# PCBA-2121-01.net
KiCad netlist of a schematic drawn in Altium Designer
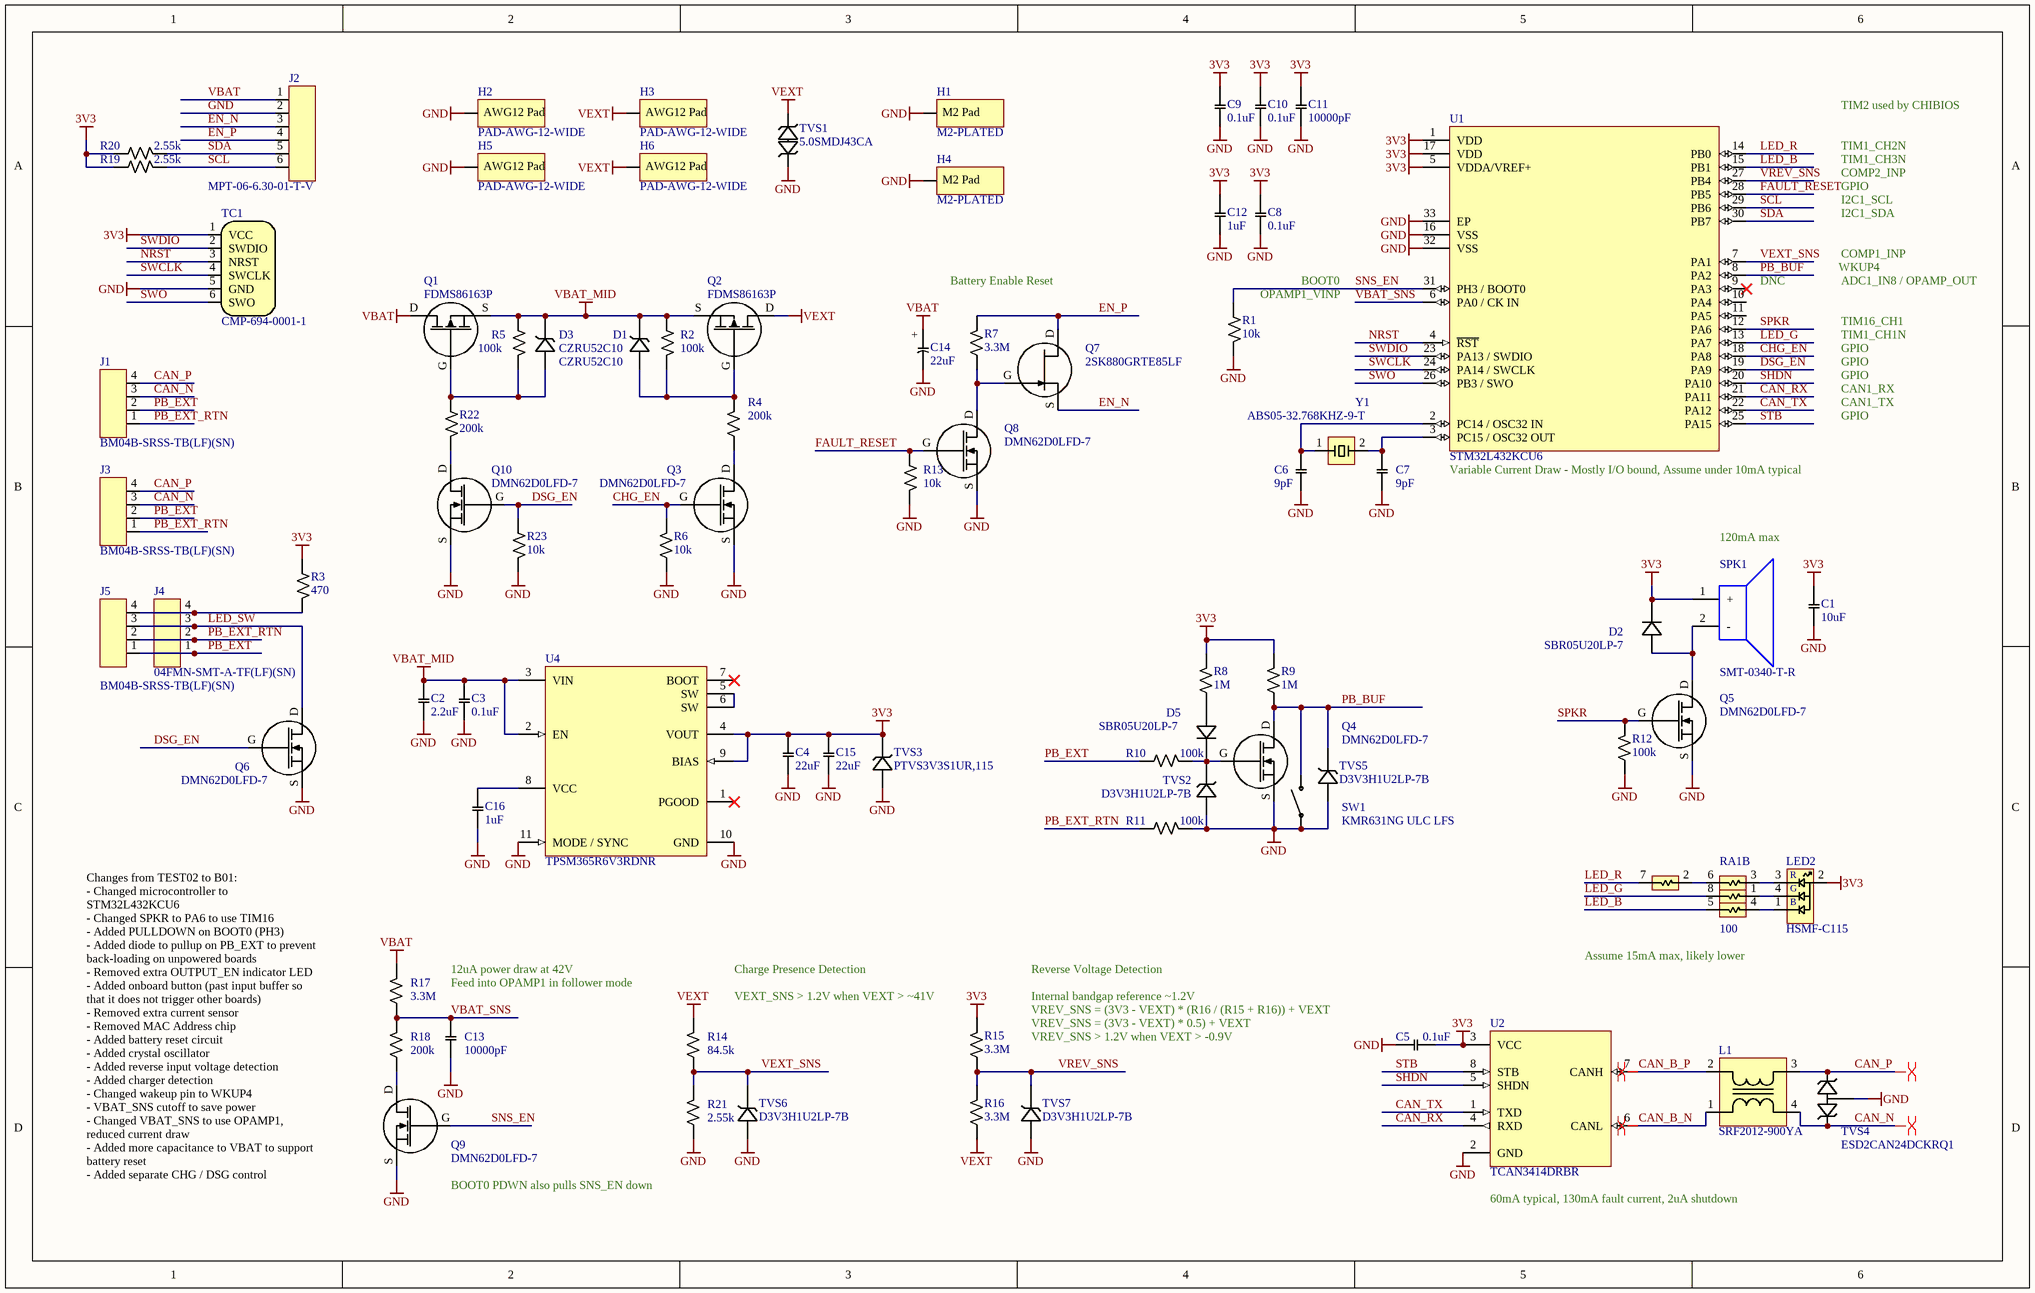
[diagram p0: PCBA-2121-01.SchDoc]

(export (version "E")
  (design (tool "Eeschema 10.0.6"))
  (components
    (comp (ref "C1")
      (value "C-10uf-X5R-16V-10%-0603")
      (footprint "C0603")
      (description "Capacitor Ceramic 10uF 16V X5R 10% SMD 0603")
      (fields (field (name "CAPACITANCE") "10uF") (field (name "TOLERANCE") "10%"))
      (libsource (lib "Hebi Robotics") (part "Capacitor"))
    )
    (comp (ref "C2")
      (value "C-2.2uf-X7R-100V-10%-1206")
      (footprint "C1206")
      (description "Capacitor Ceramic 2.2uF 100V X7R 10% SMD 1206")
      (fields (field (name "CAPACITANCE") "2.2uF") (field (name "TOLERANCE") "±10%"))
      (libsource (lib "Hebi Robotics") (part "Capacitor"))
    )
    (comp (ref "C3")
      (value "C-0.1uf-X7R-100V-10%-0603")
      (footprint "C0603")
      (description "Capacitor Ceramic 0.1uF 100V X7R 10% SMD 0603")
      (fields (field (name "CAPACITANCE") "0.1uF") (field (name "TOLERANCE") "±10%"))
      (libsource (lib "Hebi Robotics") (part "Capacitor"))
    )
    (comp (ref "C4")
      (value "C-22uf-X5R-25V-20%-1206")
      (footprint "C1206")
      (description "Capacitor Ceramic 22uF 25V X5R 20% SMD 1206")
      (fields (field (name "CAPACITANCE") "22uF") (field (name "TOLERANCE") "20%"))
      (libsource (lib "Hebi Robotics") (part "Capacitor"))
    )
    (comp (ref "C5")
      (value "C-0.1uf-X7R-25V-10%-0402")
      (footprint "C0402")
      (description "Capacitor Ceramic 0.1uF 25V X7R 10% SMD 0402")
      (fields (field (name "CAPACITANCE") "0.1uF") (field (name "TOLERANCE") "10%"))
      (libsource (lib "Hebi Robotics") (part "Capacitor"))
    )
    (comp (ref "C6")
      (value "C-9pf-NP0-50V-0.1pF-0402")
      (footprint "C0402")
      (description "Capacitor Ceramic 9pF 50V NP0 ±0.1pF SMD 0402")
      (fields (field (name "CAPACITANCE") "9pF") (field (name "TOLERANCE") "±0.1pF"))
      (libsource (lib "Hebi Robotics") (part "Capacitor"))
    )
    (comp (ref "C7")
      (value "C-9pf-NP0-50V-0.1pF-0402")
      (footprint "C0402")
      (description "Capacitor Ceramic 9pF 50V NP0 ±0.1pF SMD 0402")
      (fields (field (name "CAPACITANCE") "9pF") (field (name "TOLERANCE") "±0.1pF"))
      (libsource (lib "Hebi Robotics") (part "Capacitor"))
    )
    (comp (ref "C8")
      (value "C-0.1uf-X7R-25V-10%-0402")
      (footprint "C0402")
      (description "Capacitor Ceramic 0.1uF 25V X7R 10% SMD 0402")
      (fields (field (name "CAPACITANCE") "0.1uF") (field (name "TOLERANCE") "10%"))
      (libsource (lib "Hebi Robotics") (part "Capacitor"))
    )
    (comp (ref "C9")
      (value "C-0.1uf-X7R-25V-10%-0402")
      (footprint "C0402")
      (description "Capacitor Ceramic 0.1uF 25V X7R 10% SMD 0402")
      (fields (field (name "CAPACITANCE") "0.1uF") (field (name "TOLERANCE") "10%"))
      (libsource (lib "Hebi Robotics") (part "Capacitor"))
    )
    (comp (ref "C10")
      (value "C-0.1uf-X7R-25V-10%-0402")
      (footprint "C0402")
      (description "Capacitor Ceramic 0.1uF 25V X7R 10% SMD 0402")
      (fields (field (name "CAPACITANCE") "0.1uF") (field (name "TOLERANCE") "10%"))
      (libsource (lib "Hebi Robotics") (part "Capacitor"))
    )
    (comp (ref "C11")
      (value "C-10000pf-X7R-50V-10%-0402")
      (footprint "C0402")
      (description "Capacitor Ceramic 10000pF 50V X7R 10% SMD 0402")
      (fields (field (name "TOLERANCE") "10%") (field (name "CAPACITANCE") "10000pF"))
      (libsource (lib "Hebi Robotics") (part "Capacitor"))
    )
    (comp (ref "C12")
      (value "C-1uf-X5R-25V-10%-0402")
      (footprint "C0402")
      (description "Capacitor Ceramic 1uF 25V X5R 10% SMD 0402")
      (fields (field (name "CAPACITANCE") "1uF") (field (name "TOLERANCE") "±10%"))
      (libsource (lib "Hebi Robotics") (part "Capacitor"))
    )
    (comp (ref "C13")
      (value "C-10000pf-X7R-50V-10%-0402")
      (footprint "C0402")
      (description "Capacitor Ceramic 10000pF 50V X7R 10% SMD 0402")
      (fields (field (name "CAPACITANCE") "10000pF") (field (name "TOLERANCE") "10%"))
      (libsource (lib "Hebi Robotics") (part "Capacitor"))
    )
    (comp (ref "C14")
      (value "UCM1H220MCL1GS")
      (footprint "CAPAE5753X61L")
      (description "CAP ALUM 22UF 20% 50V SMD")
      (fields
        (field (name "CAPACITANCE") "22uF")
        (field (name "TOLERANCE") "20%")
        (field (name "VOLTAGE") "50V")
      )
      (libsource (lib "Hebi Robotics") (part "Capacitor_Polarized"))
    )
    (comp (ref "C15")
      (value "C-22uf-X5R-25V-20%-1206")
      (footprint "C1206")
      (description "Capacitor Ceramic 22uF 25V X5R 20% SMD 1206")
      (fields (field (name "CAPACITANCE") "22uF") (field (name "TOLERANCE") "20%"))
      (libsource (lib "Hebi Robotics") (part "Capacitor"))
    )
    (comp (ref "C16")
      (value "C-1uf-X5R-25V-10%-0402")
      (footprint "C0402")
      (description "Capacitor Ceramic 1uF 25V X5R 10% SMD 0402")
      (fields (field (name "CAPACITANCE") "1uF") (field (name "TOLERANCE") "±10%"))
      (libsource (lib "Hebi Robotics") (part "Capacitor"))
    )
    (comp (ref "D1")
      (value "CZRU52C10")
      (footprint "CZRU52C10")
      (description "DIODE ZENER 10V 150MW 0603")
      (libsource (lib "Hebi Robotics") (part "ZENER"))
    )
    (comp (ref "D2")
      (value "SBR05U20LP-7")
      (footprint "DFN1006-2_DIODES")
      (description "DIODE SBR 20V 500MA 2DFN")
      (libsource (lib "Hebi Robotics") (part "DIODE"))
    )
    (comp (ref "D3")
      (value "CZRU52C10")
      (footprint "CZRU52C10")
      (description "DIODE ZENER 10V 150MW 0603")
      (libsource (lib "Hebi Robotics") (part "ZENER"))
    )
    (comp (ref "D5")
      (value "SBR05U20LP-7")
      (footprint "DFN1006-2_DIODES")
      (description "DIODE SBR 20V 500MA 2DFN")
      (libsource (lib "Hebi Robotics") (part "DIODE"))
    )
    (comp (ref "H1")
      (value "M2-PLATED")
      (footprint "M2-PLATED-NORMAL")
      (description "M2 Size Screw Hole, Normal Fit, Plated")
      (libsource (lib "Hebi Robotics") (part "MOUNTING_HOLE"))
    )
    (comp (ref "H2")
      (value "PAD-AWG-12-WIDE")
      (footprint "AWG-12-With-Wire")
      (description "AWG 12 Hole with Wider Pad")
      (libsource (lib "Hebi Robotics") (part "WIRE_PAD"))
    )
    (comp (ref "H3")
      (value "PAD-AWG-12-WIDE")
      (footprint "AWG-12-With-Wire")
      (description "AWG 12 Hole with Wider Pad")
      (libsource (lib "Hebi Robotics") (part "WIRE_PAD"))
    )
    (comp (ref "H4")
      (value "M2-PLATED")
      (footprint "M2-PLATED-NORMAL")
      (description "M2 Size Screw Hole, Normal Fit, Plated")
      (libsource (lib "Hebi Robotics") (part "MOUNTING_HOLE"))
    )
    (comp (ref "H5")
      (value "PAD-AWG-12-WIDE")
      (footprint "AWG-12-With-Wire")
      (description "AWG 12 Hole with Wider Pad")
      (libsource (lib "Hebi Robotics") (part "WIRE_PAD"))
    )
    (comp (ref "H6")
      (value "PAD-AWG-12-WIDE")
      (footprint "AWG-12-With-Wire")
      (description "AWG 12 Hole with Wider Pad")
      (libsource (lib "Hebi Robotics") (part "WIRE_PAD"))
    )
    (comp (ref "J1")
      (value "BM04B-SRSS-TB(LF)(SN)")
      (footprint "BM04B-SRSS-TB")
      (description "CONN HEADER SH 4POS TOP 1MM TIN")
      (fields (field (name "MANUFACTURER") "JST Sales America Inc"))
      (libsource (lib "Hebi Robotics") (part "CONN_1_ROW_004_POS"))
    )
    (comp (ref "J2")
      (value "MPT-06-6.30-01-T-V")
      (footprint "MPT-06-6.30-01-T-V-Footprint-1")
      (description "5.00 MM POWERSTRIP/30 A DUAL BL")
      (libsource (lib "Hebi Robotics") (part "CONN_1_ROW_006_POS"))
    )
    (comp (ref "J3")
      (value "BM04B-SRSS-TB(LF)(SN)")
      (footprint "BM04B-SRSS-TB")
      (description "CONN HEADER SH 4POS TOP 1MM TIN")
      (fields (field (name "MANUFACTURER") "JST Sales America Inc"))
      (libsource (lib "Hebi Robotics") (part "CONN_1_ROW_004_POS"))
    )
    (comp (ref "J4")
      (value "04FMN-SMT-A-TF(LF)(SN)")
      (footprint "04FMN-SMT-A-TF(LF)(SN)-Footprint-1")
      (description "Ffc / Fpc Board Connector, Fmn Series, Surface Mount, Receptacle, 4, 1 Mm Rohs Compliant: Yes")
      (libsource (lib "Hebi Robotics") (part "CONN_1_ROW_004_POS"))
    )
    (comp (ref "J5")
      (value "BM04B-SRSS-TB(LF)(SN)")
      (footprint "BM04B-SRSS-TB")
      (description "CONN HEADER SH 4POS TOP 1MM TIN")
      (fields (field (name "MANUFACTURER") "JST Sales America Inc"))
      (libsource (lib "Hebi Robotics") (part "CONN_1_ROW_004_POS"))
    )
    (comp (ref "L1")
      (value "SRF2012-900YA")
      (footprint "FP-SRF2012A-MFG")
      (description "CMC 400MA 2LN 90 OHM SMD")
      (libsource (lib "Hebi Robotics") (part "CM_CHOKE_4PIN"))
    )
    (comp (ref "LED2")
      (value "HSMF-C115")
      (footprint "HSMF-C115")
      (description "LED RGB DIFFUSED CHIP SMD R/A")
      (libsource (lib "Hebi Robotics") (part "HSMF-C115"))
    )
    (comp (ref "Q1")
      (value "FDMS86163P")
      (footprint "FDMS86300DC")
      (description "MOSFET P-CH 100V 7.9A POWER56")
      (libsource (lib "Hebi Robotics") (part "P_MOSFET"))
    )
    (comp (ref "Q2")
      (value "FDMS86163P")
      (footprint "FDMS86300DC")
      (description "MOSFET P-CH 100V 7.9A POWER56")
      (libsource (lib "Hebi Robotics") (part "P_MOSFET"))
    )
    (comp (ref "Q3")
      (value "DMN62D0LFD-7")
      (footprint "DMN62D0LFD-7-Footprint-1")
      (description "MOSFET N-CH 60V 310MA 3DFN")
      (libsource (lib "Hebi Robotics") (part "N_MOSFET"))
    )
    (comp (ref "Q4")
      (value "DMN62D0LFD-7")
      (footprint "DMN62D0LFD-7-Footprint-1")
      (description "MOSFET N-CH 60V 310MA 3DFN")
      (libsource (lib "Hebi Robotics") (part "N_MOSFET"))
    )
    (comp (ref "Q5")
      (value "DMN62D0LFD-7")
      (footprint "DMN62D0LFD-7-Footprint-1")
      (description "MOSFET N-CH 60V 310MA 3DFN")
      (libsource (lib "Hebi Robotics") (part "N_MOSFET"))
    )
    (comp (ref "Q6")
      (value "DMN62D0LFD-7")
      (footprint "DMN62D0LFD-7-Footprint-1")
      (description "MOSFET N-CH 60V 310MA 3DFN")
      (libsource (lib "Hebi Robotics") (part "N_MOSFET"))
    )
    (comp (ref "Q7")
      (value "2SK880GRTE85LF")
      (footprint "SOT65P205X100-3L")
      (description "JFET N-CH 50V SC70")
      (libsource (lib "Hebi Robotics") (part "N_JFET"))
    )
    (comp (ref "Q8")
      (value "DMN62D0LFD-7")
      (footprint "DMN62D0LFD-7-Footprint-1")
      (description "MOSFET N-CH 60V 310MA 3DFN")
      (libsource (lib "Hebi Robotics") (part "N_MOSFET"))
    )
    (comp (ref "Q9")
      (value "DMN62D0LFD-7")
      (footprint "DMN62D0LFD-7-Footprint-1")
      (description "MOSFET N-CH 60V 310MA 3DFN")
      (libsource (lib "Hebi Robotics") (part "N_MOSFET"))
    )
    (comp (ref "Q10")
      (value "DMN62D0LFD-7")
      (footprint "DMN62D0LFD-7-Footprint-1")
      (description "MOSFET N-CH 60V 310MA 3DFN")
      (libsource (lib "Hebi Robotics") (part "N_MOSFET"))
    )
    (comp (ref "R1")
      (value "R-10k-1%-0.063w-0402")
      (footprint "R0402")
      (description "Resistor 0402 10k Ohm 1% 1-16 Watt")
      (fields
        (field (name "POWER") "0.063W, 1/16W")
        (field (name "RESISTANCE") "10k")
        (field (name "TOLERANCE") "1%")
      )
      (libsource (lib "Hebi Robotics") (part "Resistor"))
    )
    (comp (ref "R2")
      (value "R-100k-1%-0.063w-0402")
      (footprint "R0402")
      (description "Resistor 0402 100k Ohm 1% 1-16 Watt")
      (fields
        (field (name "POWER") "0.063W, 1/16W")
        (field (name "RESISTANCE") "100k")
        (field (name "TOLERANCE") "1%")
      )
      (libsource (lib "Hebi Robotics") (part "Resistor"))
    )
    (comp (ref "R3")
      (value "R-470-1%-0.063w-0402")
      (footprint "R0402")
      (description "Resistor 0402 470 Ohm 1% 1-16 Watt")
      (fields
        (field (name "POWER") "0.063W, 1/16W")
        (field (name "TOLERANCE") "1%")
        (field (name "RESISTANCE") "470")
      )
      (libsource (lib "Hebi Robotics") (part "Resistor"))
    )
    (comp (ref "R4")
      (value "R-200k-1%-0.063w-0402")
      (footprint "R0402")
      (description "Resistor 0402 200k Ohm 1% 1-16 Watt")
      (fields
        (field (name "POWER") "0.063W, 1/16W")
        (field (name "RESISTANCE") "200k")
        (field (name "TOLERANCE") "1%")
      )
      (libsource (lib "Hebi Robotics") (part "Resistor"))
    )
    (comp (ref "R5")
      (value "R-100k-1%-0.063w-0402")
      (footprint "R0402")
      (description "Resistor 0402 100k Ohm 1% 1-16 Watt")
      (fields
        (field (name "POWER") "0.063W, 1/16W")
        (field (name "RESISTANCE") "100k")
        (field (name "TOLERANCE") "1%")
      )
      (libsource (lib "Hebi Robotics") (part "Resistor"))
    )
    (comp (ref "R6")
      (value "R-10k-1%-0.063w-0402")
      (footprint "R0402")
      (description "Resistor 0402 10k Ohm 1% 1-16 Watt")
      (fields
        (field (name "POWER") "0.063W, 1/16W")
        (field (name "RESISTANCE") "10k")
        (field (name "TOLERANCE") "1%")
      )
      (libsource (lib "Hebi Robotics") (part "Resistor"))
    )
    (comp (ref "R7")
      (value "R-3.3M-1%-0.063w-0402")
      (footprint "R0402")
      (description "Resistor 0402 3.3M Ohm 1% 1-16 Watt")
      (fields (field (name "POWER") "0.063W, 1/16W") (field (name "RESISTANCE") "3.3M"))
      (libsource (lib "Hebi Robotics") (part "Resistor"))
    )
    (comp (ref "R8")
      (value "R-1M-1%-0.063w-0402")
      (footprint "R0402")
      (description "Resistor 0402 1M Ohm 1% 1-16 Watt")
      (fields
        (field (name "RESISTANCE") "1M")
        (field (name "POWER") "0.063W, 1/16W")
        (field (name "TOLERANCE") "1%")
      )
      (libsource (lib "Hebi Robotics") (part "Resistor"))
    )
    (comp (ref "R9")
      (value "R-1M-1%-0.063w-0402")
      (footprint "R0402")
      (description "Resistor 0402 1M Ohm 1% 1-16 Watt")
      (fields
        (field (name "RESISTANCE") "1M")
        (field (name "POWER") "0.063W, 1/16W")
        (field (name "TOLERANCE") "1%")
      )
      (libsource (lib "Hebi Robotics") (part "Resistor"))
    )
    (comp (ref "R10")
      (value "R-100k-1%-0.063w-0402")
      (footprint "R0402")
      (description "Resistor 0402 100k Ohm 1% 1-16 Watt")
      (fields
        (field (name "POWER") "0.063W, 1/16W")
        (field (name "RESISTANCE") "100k")
        (field (name "TOLERANCE") "1%")
      )
      (libsource (lib "Hebi Robotics") (part "Resistor"))
    )
    (comp (ref "R11")
      (value "R-100k-1%-0.063w-0402")
      (footprint "R0402")
      (description "Resistor 0402 100k Ohm 1% 1-16 Watt")
      (fields
        (field (name "POWER") "0.063W, 1/16W")
        (field (name "RESISTANCE") "100k")
        (field (name "TOLERANCE") "1%")
      )
      (libsource (lib "Hebi Robotics") (part "Resistor"))
    )
    (comp (ref "R12")
      (value "R-100k-1%-0.063w-0402")
      (footprint "R0402")
      (description "Resistor 0402 100k Ohm 1% 1-16 Watt")
      (fields
        (field (name "POWER") "0.063W, 1/16W")
        (field (name "TOLERANCE") "1%")
        (field (name "RESISTANCE") "100k")
      )
      (libsource (lib "Hebi Robotics") (part "Resistor"))
    )
    (comp (ref "R13")
      (value "R-10k-1%-0.063w-0402")
      (footprint "R0402")
      (description "Resistor 0402 10k Ohm 1% 1-16 Watt")
      (fields
        (field (name "POWER") "0.063W, 1/16W")
        (field (name "RESISTANCE") "10k")
        (field (name "TOLERANCE") "1%")
      )
      (libsource (lib "Hebi Robotics") (part "Resistor"))
    )
    (comp (ref "R14")
      (value "R-84.5k-1%-0.063w-0402")
      (footprint "R0402")
      (description "Resistor 0402 84.5k Ohm 1% 1-16 Watt")
      (fields (field (name "RESISTANCE") "84.5k") (field (name "POWER") "0.063W, 1/16W"))
      (libsource (lib "Hebi Robotics") (part "Resistor"))
    )
    (comp (ref "R15")
      (value "R-3.3M-1%-0.063w-0402")
      (footprint "R0402")
      (description "Resistor 0402 3.3M Ohm 1% 1-16 Watt")
      (fields (field (name "POWER") "0.063W, 1/16W") (field (name "RESISTANCE") "3.3M"))
      (libsource (lib "Hebi Robotics") (part "Resistor"))
    )
    (comp (ref "R16")
      (value "R-3.3M-1%-0.063w-0402")
      (footprint "R0402")
      (description "Resistor 0402 3.3M Ohm 1% 1-16 Watt")
      (fields (field (name "POWER") "0.063W, 1/16W") (field (name "RESISTANCE") "3.3M"))
      (libsource (lib "Hebi Robotics") (part "Resistor"))
    )
    (comp (ref "R17")
      (value "R-3.3M-1%-0.063w-0402")
      (footprint "R0402")
      (description "Resistor 0402 3.3M Ohm 1% 1-16 Watt")
      (fields (field (name "POWER") "0.063W, 1/16W") (field (name "RESISTANCE") "3.3M"))
      (libsource (lib "Hebi Robotics") (part "Resistor"))
    )
    (comp (ref "R18")
      (value "R-200k-1%-0.063w-0402")
      (footprint "R0402")
      (description "Resistor 0402 200k Ohm 1% 1-16 Watt")
      (fields
        (field (name "POWER") "0.063W, 1/16W")
        (field (name "RESISTANCE") "200k")
        (field (name "TOLERANCE") "1%")
      )
      (libsource (lib "Hebi Robotics") (part "Resistor"))
    )
    (comp (ref "R19")
      (value "R-2.55k-1%-0.063w-0402")
      (footprint "R0402")
      (description "Resistor 0402 2.55k Ohm 1% 1-16 Watt")
      (fields (field (name "RESISTANCE") "2.55k") (field (name "POWER") "0.063W, 1/16W"))
      (libsource (lib "Hebi Robotics") (part "Resistor"))
    )
    (comp (ref "R20")
      (value "R-2.55k-1%-0.063w-0402")
      (footprint "R0402")
      (description "Resistor 0402 2.55k Ohm 1% 1-16 Watt")
      (fields (field (name "RESISTANCE") "2.55k") (field (name "POWER") "0.063W, 1/16W"))
      (libsource (lib "Hebi Robotics") (part "Resistor"))
    )
    (comp (ref "R21")
      (value "R-2.55k-1%-0.063w-0402")
      (footprint "R0402")
      (description "Resistor 0402 2.55k Ohm 1% 1-16 Watt")
      (fields (field (name "POWER") "0.063W, 1/16W") (field (name "RESISTANCE") "2.55k"))
      (libsource (lib "Hebi Robotics") (part "Resistor"))
    )
    (comp (ref "R22")
      (value "R-200k-1%-0.063w-0402")
      (footprint "R0402")
      (description "Resistor 0402 200k Ohm 1% 1-16 Watt")
      (fields
        (field (name "POWER") "0.063W, 1/16W")
        (field (name "RESISTANCE") "200k")
        (field (name "TOLERANCE") "1%")
      )
      (libsource (lib "Hebi Robotics") (part "Resistor"))
    )
    (comp (ref "R23")
      (value "R-10k-1%-0.063w-0402")
      (footprint "R0402")
      (description "Resistor 0402 10k Ohm 1% 1-16 Watt")
      (fields
        (field (name "POWER") "0.063W, 1/16W")
        (field (name "RESISTANCE") "10k")
        (field (name "TOLERANCE") "1%")
      )
      (libsource (lib "Hebi Robotics") (part "Resistor"))
    )
    (comp (ref "RA1")
      (value "RA-4-C-100-5%-0.063w-0804")
      (footprint "741C083")
      (description "100 ohm Resistor Array 4 Element Concave 5%  1-16Watt 0804")
      (fields (field (name "POWER") "0.063W") (field (name "RESISTANCE") "100"))
      (libsource (lib "Hebi Robotics") (part "RA4"))
    )
    (comp (ref "SPK1")
      (value "SMT-0340-T-R")
      (footprint "SMT-0340-T-R")
      (description "BUZZER MAGNETIC 3V 3.2X3.2MM SMD")
      (fields (field (name "VOLTAGE") "3V"))
      (libsource (lib "Hebi Robotics") (part "Speaker"))
    )
    (comp (ref "SW1")
      (value "KMR631NG ULC LFS")
      (footprint "KMR6_CK")
      (description "SWITCH TACTILE SPST-NO 50MA 32V")
      (fields (field (name "MANUFACTURER") "ITT C&K"))
      (libsource (lib "Hebi Robotics") (part "SPST_NO"))
    )
    (comp (ref "TC1")
      (value "CMP-694-0001-1")
      (footprint "TC2030-MCP-NL_SMALL")
      (description "TC2030-MCP-NL")
      (fields (field (name "MANUFACTURER PART NUMBER") "TC2030-MCP-NL_SMALL"))
      (libsource (lib "Hebi Robotics") (part "TC2030-MCP-NL"))
    )
    (comp (ref "TVS1")
      (value "5.0SMDJ43CA")
      (footprint "DIOM6959X26L")
      (description "TVS DIODE 43VWM 69.4VC DO214AB")
      (libsource (lib "Hebi Robotics") (part "TVS_BI"))
    )
    (comp (ref "TVS2")
      (value "D3V3H1U2LP-7B")
      (footprint "DFN70P101X53-2N")
      (description "TVS DIODE 3.3V 10V DFN1006-2")
      (libsource (lib "Hebi Robotics") (part "TVS"))
    )
    (comp (ref "TVS3")
      (value "PTVS3V3S1UR,115")
      (footprint "SOD-123W_NXP")
      (description "TVS DIODE 3.3VWM 8VC SOD123W")
      (libsource (lib "Hebi Robotics") (part "TVS"))
    )
    (comp (ref "TVS4")
      (value "ESD2CAN24DCKRQ1")
      (footprint "SOT65P210X90-3L")
      (description "TVS DIODE 24VWM 37VC CAN SC703")
      (libsource (lib "Hebi Robotics") (part "ESD2CAN24DCKRQ1-Symbol-1"))
    )
    (comp (ref "TVS5")
      (value "D3V3H1U2LP-7B")
      (footprint "DFN70P101X53-2N")
      (description "TVS DIODE 3.3V 10V DFN1006-2")
      (libsource (lib "Hebi Robotics") (part "TVS"))
    )
    (comp (ref "TVS6")
      (value "D3V3H1U2LP-7B")
      (footprint "DFN70P101X53-2N")
      (description "TVS DIODE 3.3V 10V DFN1006-2")
      (libsource (lib "Hebi Robotics") (part "TVS"))
    )
    (comp (ref "TVS7")
      (value "D3V3H1U2LP-7B")
      (footprint "DFN70P101X53-2N")
      (description "TVS DIODE 3.3V 10V DFN1006-2")
      (libsource (lib "Hebi Robotics") (part "TVS"))
    )
    (comp (ref "U1")
      (value "STM32L432KCU6")
      (footprint "QFN50P500X500X60_HS-33L")
      (description "IC MCU 32BIT 256KB FLSH 32UFQFPN")
      (libsource (lib "Hebi Robotics") (part "STM32L412K8U6"))
    )
    (comp (ref "U2")
      (value "TCAN3414DRBR")
      (footprint "SON65P300X100_HS-9L")
      (description "IC TRANSCEIVER HALF 1/1 8SON")
      (libsource (lib "Hebi Robotics") (part "TCAN3414DRBR-Symbol-1"))
    )
    (comp (ref "U4")
      (value "TPSM365R6V3RDNR")
      (footprint "TPSM365R6V3RDNR-Footprint-1")
      (description "3-V TO 65-V INPUT, 3V3 OUT, 300mA")
      (libsource (lib "Hebi Robotics") (part "TPSM365R6V3RDNR-Symbol-1"))
    )
    (comp (ref "Y1")
      (value "ABS05-32.768KHZ-9-T")
      (footprint "ABS05-32.768KHZ-9-T-Footprint-1")
      (description "CRYSTAL 32.7680KHZ 9PF SMD")
      (libsource (lib "Hebi Robotics") (part "CRYSTAL"))
    )
  )
  (nets
    (net (code "1") (name "/CAN_B_N") (class "Default")
      (node (ref "L1") (pin "1") (pinfunction "1_1") (pintype "passive"))
      (node (ref "U2") (pin "6") (pinfunction "CANL_6") (pintype "bidirectional"))
    )
    (net (code "2") (name "/CAN_B_P") (class "Default")
      (node (ref "L1") (pin "2") (pinfunction "2_2") (pintype "passive"))
      (node (ref "U2") (pin "7") (pinfunction "CANH_7") (pintype "bidirectional"))
    )
    (net (code "3") (name "/CAN_N") (class "Default")
      (node (ref "J1") (pin "3") (pinfunction "3_3") (pintype "passive"))
      (node (ref "J3") (pin "3") (pinfunction "3_3") (pintype "passive"))
      (node (ref "L1") (pin "4") (pinfunction "4_4") (pintype "passive"))
      (node (ref "TVS4") (pin "2") (pinfunction "2_2") (pintype "passive"))
    )
    (net (code "4") (name "/CAN_P") (class "Default")
      (node (ref "J1") (pin "4") (pinfunction "4_4") (pintype "passive"))
      (node (ref "J3") (pin "4") (pinfunction "4_4") (pintype "passive"))
      (node (ref "L1") (pin "3") (pinfunction "3_3") (pintype "passive"))
      (node (ref "TVS4") (pin "1") (pinfunction "1_1") (pintype "passive"))
    )
    (net (code "5") (name "/CAN_RX") (class "Default")
      (node (ref "U1") (pin "21") (pinfunction "PA11_21") (pintype "bidirectional"))
      (node (ref "U2") (pin "4") (pinfunction "RXD_4") (pintype "output"))
    )
    (net (code "6") (name "/CAN_TX") (class "Default")
      (node (ref "U1") (pin "22") (pinfunction "PA12_22") (pintype "bidirectional"))
      (node (ref "U2") (pin "1") (pinfunction "TXD_1") (pintype "input"))
    )
    (net (code "7") (name "/CHG_EN") (class "Default")
      (node (ref "Q3") (pin "G") (pinfunction "G_G") (pintype "passive"))
      (node (ref "R6") (pin "2") (pinfunction "2_2") (pintype "passive"))
      (node (ref "U1") (pin "18") (pinfunction "PA8_18") (pintype "bidirectional"))
    )
    (net (code "8") (name "/DSG_EN") (class "Default")
      (node (ref "Q10") (pin "G") (pinfunction "G_G") (pintype "passive"))
      (node (ref "Q6") (pin "G") (pinfunction "G_G") (pintype "passive"))
      (node (ref "R23") (pin "2") (pinfunction "2_2") (pintype "passive"))
      (node (ref "U1") (pin "19") (pinfunction "PA9_19") (pintype "bidirectional"))
    )
    (net (code "9") (name "/EN_N") (class "Default")
      (node (ref "J2") (pin "3") (pinfunction "3_3") (pintype "passive"))
      (node (ref "Q7") (pin "S") (pinfunction "S_S") (pintype "passive"))
    )
    (net (code "10") (name "/EN_P") (class "Default")
      (node (ref "J2") (pin "4") (pinfunction "4_4") (pintype "passive"))
      (node (ref "Q7") (pin "D") (pinfunction "D_D") (pintype "passive"))
      (node (ref "R7") (pin "2") (pinfunction "2_2") (pintype "passive"))
    )
    (net (code "11") (name "/FAULT_RESET") (class "Default")
      (node (ref "Q8") (pin "G") (pinfunction "G_G") (pintype "passive"))
      (node (ref "R13") (pin "1") (pinfunction "1_1") (pintype "passive"))
      (node (ref "U1") (pin "28") (pinfunction "PB5_28") (pintype "bidirectional"))
    )
    (net (code "12") (name "/LED_B") (class "Default")
      (node (ref "RA1") (pin "5") (pinfunction "5_5") (pintype "passive"))
      (node (ref "U1") (pin "15") (pinfunction "PB1_15") (pintype "bidirectional"))
    )
    (net (code "13") (name "/LED_G") (class "Default")
      (node (ref "RA1") (pin "8") (pinfunction "8_8") (pintype "passive"))
      (node (ref "U1") (pin "13") (pinfunction "PA7_13") (pintype "bidirectional"))
    )
    (net (code "14") (name "/LED_R") (class "Default")
      (node (ref "RA1") (pin "7") (pinfunction "7_7") (pintype "passive"))
      (node (ref "U1") (pin "14") (pinfunction "PB0_14") (pintype "bidirectional"))
    )
    (net (code "15") (name "/LED_SW") (class "Default")
      (node (ref "J4") (pin "3") (pinfunction "3_3") (pintype "passive"))
      (node (ref "J5") (pin "3") (pinfunction "3_3") (pintype "passive"))
      (node (ref "Q6") (pin "D") (pinfunction "D_D") (pintype "passive"))
    )
    (net (code "16") (name "/NRST") (class "Default")
      (node (ref "TC1") (pin "3") (pinfunction "NRST_3") (pintype "passive"))
      (node (ref "U1") (pin "4") (pinfunction "~{RST}_4") (pintype "input"))
    )
    (net (code "17") (name "/PB_BUF") (class "Default")
      (node (ref "Q4") (pin "D") (pinfunction "D_D") (pintype "passive"))
      (node (ref "R9") (pin "1") (pinfunction "1_1") (pintype "passive"))
      (node (ref "SW1") (pin "2") (pinfunction "2_2") (pintype "passive"))
      (node (ref "TVS5") (pin "C") (pinfunction "C_C") (pintype "passive"))
      (node (ref "U1") (pin "8") (pinfunction "PA2_8") (pintype "bidirectional"))
    )
    (net (code "18") (name "/PB_EXT") (class "Default")
      (node (ref "J1") (pin "2") (pinfunction "2_2") (pintype "passive"))
      (node (ref "J3") (pin "2") (pinfunction "2_2") (pintype "passive"))
      (node (ref "J4") (pin "1") (pinfunction "1_1") (pintype "passive"))
      (node (ref "J5") (pin "1") (pinfunction "1_1") (pintype "passive"))
      (node (ref "R10") (pin "1") (pinfunction "1_1") (pintype "passive"))
    )
    (net (code "19") (name "/PB_EXT_RTN") (class "Default")
      (node (ref "J1") (pin "1") (pinfunction "1_1") (pintype "passive"))
      (node (ref "J3") (pin "1") (pinfunction "1_1") (pintype "passive"))
      (node (ref "J4") (pin "2") (pinfunction "2_2") (pintype "passive"))
      (node (ref "J5") (pin "2") (pinfunction "2_2") (pintype "passive"))
      (node (ref "R11") (pin "1") (pinfunction "1_1") (pintype "passive"))
    )
    (net (code "20") (name "/SCL") (class "Default")
      (node (ref "J2") (pin "6") (pinfunction "6_6") (pintype "passive"))
      (node (ref "R19") (pin "2") (pinfunction "2_2") (pintype "passive"))
      (node (ref "U1") (pin "29") (pinfunction "PB6_29") (pintype "bidirectional"))
    )
    (net (code "21") (name "/SDA") (class "Default")
      (node (ref "J2") (pin "5") (pinfunction "5_5") (pintype "passive"))
      (node (ref "R20") (pin "2") (pinfunction "2_2") (pintype "passive"))
      (node (ref "U1") (pin "30") (pinfunction "PB7_30") (pintype "bidirectional"))
    )
    (net (code "22") (name "/SHDN") (class "Default")
      (node (ref "U1") (pin "20") (pinfunction "PA10_20") (pintype "bidirectional"))
      (node (ref "U2") (pin "5") (pinfunction "SHDN_5") (pintype "input"))
    )
    (net (code "23") (name "/SNS_EN") (class "Default")
      (node (ref "Q9") (pin "G") (pinfunction "G_G") (pintype "passive"))
      (node (ref "R1") (pin "1") (pinfunction "1_1") (pintype "passive"))
      (node (ref "U1") (pin "31") (pinfunction "PH3_/_BOOT0_31") (pintype "bidirectional"))
    )
    (net (code "24") (name "/SPKR") (class "Default")
      (node (ref "Q5") (pin "G") (pinfunction "G_G") (pintype "passive"))
      (node (ref "R12") (pin "2") (pinfunction "2_2") (pintype "passive"))
      (node (ref "U1") (pin "12") (pinfunction "PA6_12") (pintype "bidirectional"))
    )
    (net (code "25") (name "/STB") (class "Default")
      (node (ref "U1") (pin "25") (pinfunction "PA15_25") (pintype "bidirectional"))
      (node (ref "U2") (pin "8") (pinfunction "STB_8") (pintype "input"))
    )
    (net (code "26") (name "/SWCLK") (class "Default")
      (node (ref "TC1") (pin "4") (pinfunction "SWCLK_4") (pintype "passive"))
      (node (ref "U1") (pin "24") (pinfunction "PA14_/_SWCLK_24") (pintype "bidirectional"))
    )
    (net (code "27") (name "/SWDIO") (class "Default")
      (node (ref "TC1") (pin "2") (pinfunction "SWDIO_2") (pintype "passive"))
      (node (ref "U1") (pin "23") (pinfunction "PA13_/_SWDIO_23") (pintype "bidirectional"))
    )
    (net (code "28") (name "/SWO") (class "Default")
      (node (ref "TC1") (pin "6") (pinfunction "SWO_6") (pintype "passive"))
      (node (ref "U1") (pin "26") (pinfunction "PB3_/_SWO_26") (pintype "bidirectional"))
    )
    (net (code "29") (name "/VBAT_SNS") (class "Default")
      (node (ref "C13") (pin "1") (pinfunction "1_1") (pintype "passive"))
      (node (ref "R17") (pin "1") (pinfunction "1_1") (pintype "passive"))
      (node (ref "R18") (pin "2") (pinfunction "2_2") (pintype "passive"))
      (node (ref "U1") (pin "6") (pinfunction "PA0_/_CK_IN_6") (pintype "bidirectional"))
    )
    (net (code "30") (name "/VEXT_SNS") (class "Default")
      (node (ref "R14") (pin "1") (pinfunction "1_1") (pintype "passive"))
      (node (ref "R21") (pin "2") (pinfunction "2_2") (pintype "passive"))
      (node (ref "TVS6") (pin "C") (pinfunction "C_C") (pintype "passive"))
      (node (ref "U1") (pin "7") (pinfunction "PA1_7") (pintype "bidirectional"))
    )
    (net (code "31") (name "/VREV_SNS") (class "Default")
      (node (ref "R15") (pin "1") (pinfunction "1_1") (pintype "passive"))
      (node (ref "R16") (pin "2") (pinfunction "2_2") (pintype "passive"))
      (node (ref "TVS7") (pin "C") (pinfunction "C_C") (pintype "passive"))
      (node (ref "U1") (pin "27") (pinfunction "PB4_27") (pintype "bidirectional"))
    )
    (net (code "32") (name "3V3") (class "Default")
      (node (ref "C1") (pin "1") (pinfunction "1_1") (pintype "passive"))
      (node (ref "C10") (pin "2") (pinfunction "2_2") (pintype "passive"))
      (node (ref "C11") (pin "2") (pinfunction "2_2") (pintype "passive"))
      (node (ref "C12") (pin "1") (pinfunction "1_1") (pintype "passive"))
      (node (ref "C15") (pin "2") (pinfunction "2_2") (pintype "passive"))
      (node (ref "C4") (pin "2") (pinfunction "2_2") (pintype "passive"))
      (node (ref "C5") (pin "2") (pinfunction "2_2") (pintype "passive"))
      (node (ref "C8") (pin "2") (pinfunction "2_2") (pintype "passive"))
      (node (ref "C9") (pin "2") (pinfunction "2_2") (pintype "passive"))
      (node (ref "D2") (pin "C") (pinfunction "C_C") (pintype "passive"))
      (node (ref "LED2") (pin "2") (pinfunction "A_2") (pintype "passive"))
      (node (ref "R15") (pin "2") (pinfunction "2_2") (pintype "passive"))
      (node (ref "R19") (pin "1") (pinfunction "1_1") (pintype "passive"))
      (node (ref "R20") (pin "1") (pinfunction "1_1") (pintype "passive"))
      (node (ref "R3") (pin "1") (pinfunction "1_1") (pintype "passive"))
      (node (ref "R8") (pin "2") (pinfunction "2_2") (pintype "passive"))
      (node (ref "R9") (pin "2") (pinfunction "2_2") (pintype "passive"))
      (node (ref "SPK1") (pin "1") (pinfunction "+_1") (pintype "passive"))
      (node (ref "TC1") (pin "1") (pinfunction "VCC_1") (pintype "passive"))
      (node (ref "TVS3") (pin "C") (pinfunction "C_C") (pintype "passive"))
      (node (ref "U1") (pin "1") (pinfunction "VDD_1") (pintype "power_in"))
      (node (ref "U1") (pin "17") (pinfunction "VDD_17") (pintype "power_in"))
      (node (ref "U1") (pin "5") (pinfunction "VDDA/VREF+_5") (pintype "power_in"))
      (node (ref "U2") (pin "3") (pinfunction "VCC_3") (pintype "power_in"))
      (node (ref "U4") (pin "4") (pinfunction "VOUT_4") (pintype "power_in"))
      (node (ref "U4") (pin "9") (pinfunction "BIAS_9") (pintype "input"))
    )
    (net (code "33") (name "GND") (class "Default")
      (node (ref "C1") (pin "2") (pinfunction "2_2") (pintype "passive"))
      (node (ref "C10") (pin "1") (pinfunction "1_1") (pintype "passive"))
      (node (ref "C11") (pin "1") (pinfunction "1_1") (pintype "passive"))
      (node (ref "C12") (pin "2") (pinfunction "2_2") (pintype "passive"))
      (node (ref "C13") (pin "2") (pinfunction "2_2") (pintype "passive"))
      (node (ref "C14") (pin "-") (pinfunction "-_-") (pintype "passive"))
      (node (ref "C15") (pin "1") (pinfunction "1_1") (pintype "passive"))
      (node (ref "C16") (pin "1") (pinfunction "1_1") (pintype "passive"))
      (node (ref "C2") (pin "1") (pinfunction "1_1") (pintype "passive"))
      (node (ref "C3") (pin "1") (pinfunction "1_1") (pintype "passive"))
      (node (ref "C4") (pin "1") (pinfunction "1_1") (pintype "passive"))
      (node (ref "C5") (pin "1") (pinfunction "1_1") (pintype "passive"))
      (node (ref "C6") (pin "1") (pinfunction "1_1") (pintype "passive"))
      (node (ref "C7") (pin "1") (pinfunction "1_1") (pintype "passive"))
      (node (ref "C8") (pin "1") (pinfunction "1_1") (pintype "passive"))
      (node (ref "C9") (pin "1") (pinfunction "1_1") (pintype "passive"))
      (node (ref "H1") (pin "HOLE") (pinfunction "HOLE_HOLE") (pintype "passive"))
      (node (ref "H2") (pin "HOLE") (pinfunction "HOLE_HOLE") (pintype "passive"))
      (node (ref "H4") (pin "HOLE") (pinfunction "HOLE_HOLE") (pintype "passive"))
      (node (ref "H5") (pin "HOLE") (pinfunction "HOLE_HOLE") (pintype "passive"))
      (node (ref "J2") (pin "2") (pinfunction "2_2") (pintype "passive"))
      (node (ref "Q10") (pin "S") (pinfunction "S_S") (pintype "passive"))
      (node (ref "Q3") (pin "S") (pinfunction "S_S") (pintype "passive"))
      (node (ref "Q4") (pin "S") (pinfunction "S_S") (pintype "passive"))
      (node (ref "Q5") (pin "S") (pinfunction "S_S") (pintype "passive"))
      (node (ref "Q6") (pin "S") (pinfunction "S_S") (pintype "passive"))
      (node (ref "Q8") (pin "S") (pinfunction "S_S") (pintype "passive"))
      (node (ref "Q9") (pin "S") (pinfunction "S_S") (pintype "passive"))
      (node (ref "R1") (pin "2") (pinfunction "2_2") (pintype "passive"))
      (node (ref "R11") (pin "2") (pinfunction "2_2") (pintype "passive"))
      (node (ref "R12") (pin "1") (pinfunction "1_1") (pintype "passive"))
      (node (ref "R13") (pin "2") (pinfunction "2_2") (pintype "passive"))
      (node (ref "R21") (pin "1") (pinfunction "1_1") (pintype "passive"))
      (node (ref "R23") (pin "1") (pinfunction "1_1") (pintype "passive"))
      (node (ref "R6") (pin "1") (pinfunction "1_1") (pintype "passive"))
      (node (ref "SW1") (pin "1") (pinfunction "1_1") (pintype "passive"))
      (node (ref "TC1") (pin "5") (pinfunction "GND_5") (pintype "passive"))
      (node (ref "TVS1") (pin "C") (pinfunction "C_C") (pintype "passive"))
      (node (ref "TVS2") (pin "A") (pinfunction "A_A") (pintype "passive"))
      (node (ref "TVS3") (pin "A") (pinfunction "A_A") (pintype "passive"))
      (node (ref "TVS4") (pin "3") (pinfunction "3_3") (pintype "passive"))
      (node (ref "TVS5") (pin "A") (pinfunction "A_A") (pintype "passive"))
      (node (ref "TVS6") (pin "A") (pinfunction "A_A") (pintype "passive"))
      (node (ref "TVS7") (pin "A") (pinfunction "A_A") (pintype "passive"))
      (node (ref "U1") (pin "16") (pinfunction "VSS_16") (pintype "power_in"))
      (node (ref "U1") (pin "32") (pinfunction "VSS_32") (pintype "power_in"))
      (node (ref "U1") (pin "33") (pinfunction "EP_33") (pintype "power_in"))
      (node (ref "U2") (pin "2") (pinfunction "GND_2") (pintype "passive"))
      (node (ref "U4") (pin "10") (pinfunction "GND_10") (pintype "passive"))
      (node (ref "U4") (pin "11") (pinfunction "MODE_/_SYNC_11") (pintype "input"))
    )
    (net (code "34") (name "Net-(D1-PadA)") (class "Default")
      (node (ref "D1") (pin "A") (pinfunction "A_A") (pintype "passive"))
      (node (ref "Q2") (pin "G") (pinfunction "G_G") (pintype "passive"))
      (node (ref "R2") (pin "2") (pinfunction "2_2") (pintype "passive"))
      (node (ref "R4") (pin "2") (pinfunction "2_2") (pintype "passive"))
    )
    (net (code "35") (name "Net-(D3-PadA)") (class "Default")
      (node (ref "D3") (pin "A") (pinfunction "A_A") (pintype "passive"))
      (node (ref "Q1") (pin "G") (pinfunction "G_G") (pintype "passive"))
      (node (ref "R22") (pin "2") (pinfunction "2_2") (pintype "passive"))
      (node (ref "R5") (pin "2") (pinfunction "2_2") (pintype "passive"))
    )
    (net (code "36") (name "Net-(D5-PadA)") (class "Default")
      (node (ref "D5") (pin "A") (pinfunction "A_A") (pintype "passive"))
      (node (ref "R8") (pin "1") (pinfunction "1_1") (pintype "passive"))
    )
    (net (code "37") (name "Net-(D5-PadC)") (class "Default")
      (node (ref "D5") (pin "C") (pinfunction "C_C") (pintype "passive"))
      (node (ref "Q4") (pin "G") (pinfunction "G_G") (pintype "passive"))
      (node (ref "R10") (pin "2") (pinfunction "2_2") (pintype "passive"))
      (node (ref "TVS2") (pin "C") (pinfunction "C_C") (pintype "passive"))
    )
    (net (code "38") (name "Net-(J4-Pad4)") (class "Default")
      (node (ref "J4") (pin "4") (pinfunction "4_4") (pintype "passive"))
      (node (ref "J5") (pin "4") (pinfunction "4_4") (pintype "passive"))
      (node (ref "R3") (pin "2") (pinfunction "2_2") (pintype "passive"))
    )
    (net (code "39") (name "Net-(LED2-CB)") (class "Default")
      (node (ref "LED2") (pin "3") (pinfunction "CB_3") (pintype "passive"))
      (node (ref "RA1") (pin "3") (pinfunction "3_3") (pintype "passive"))
    )
    (net (code "40") (name "Net-(LED2-CG)") (class "Default")
      (node (ref "LED2") (pin "4") (pinfunction "CG_4") (pintype "passive"))
      (node (ref "RA1") (pin "1") (pinfunction "1_1") (pintype "passive"))
    )
    (net (code "41") (name "Net-(LED2-CR)") (class "Default")
      (node (ref "LED2") (pin "1") (pinfunction "CR_1") (pintype "passive"))
      (node (ref "RA1") (pin "4") (pinfunction "4_4") (pintype "passive"))
    )
    (net (code "42") (name "Net-(Q3-PadD)") (class "Default")
      (node (ref "Q3") (pin "D") (pinfunction "D_D") (pintype "passive"))
      (node (ref "R4") (pin "1") (pinfunction "1_1") (pintype "passive"))
    )
    (net (code "43") (name "Net-(Q7-PadG)") (class "Default")
      (node (ref "Q7") (pin "G") (pinfunction "G_G") (pintype "passive"))
      (node (ref "Q8") (pin "D") (pinfunction "D_D") (pintype "passive"))
      (node (ref "R7") (pin "1") (pinfunction "1_1") (pintype "passive"))
    )
    (net (code "44") (name "Net-(Q9-PadD)") (class "Default")
      (node (ref "Q9") (pin "D") (pinfunction "D_D") (pintype "passive"))
      (node (ref "R18") (pin "1") (pinfunction "1_1") (pintype "passive"))
    )
    (net (code "45") (name "Net-(Q10-PadD)") (class "Default")
      (node (ref "Q10") (pin "D") (pinfunction "D_D") (pintype "passive"))
      (node (ref "R22") (pin "1") (pinfunction "1_1") (pintype "passive"))
    )
    (net (code "46") (name "Net-(RA1-Pad2)") (class "Default")
      (node (ref "RA1") (pin "2") (pinfunction "2_2") (pintype "passive"))
      (node (ref "RA1") (pin "6") (pinfunction "6_6") (pintype "passive"))
    )
    (net (code "47") (name "Net-(SPK1--)") (class "Default")
      (node (ref "D2") (pin "A") (pinfunction "A_A") (pintype "passive"))
      (node (ref "Q5") (pin "D") (pinfunction "D_D") (pintype "passive"))
      (node (ref "SPK1") (pin "2") (pinfunction "-_2") (pintype "passive"))
    )
    (net (code "48") (name "Net-(U1-PC14_{slash}_OSC32_IN)") (class "Default")
      (node (ref "C6") (pin "2") (pinfunction "2_2") (pintype "passive"))
      (node (ref "U1") (pin "2") (pinfunction "PC14_/_OSC32_IN_2") (pintype "bidirectional"))
      (node (ref "Y1") (pin "1") (pinfunction "1_1") (pintype "passive"))
    )
    (net (code "49") (name "Net-(U1-PC15_{slash}_OSC32_OUT)") (class "Default")
      (node (ref "C7") (pin "2") (pinfunction "2_2") (pintype "passive"))
      (node (ref "U1") (pin "3") (pinfunction "PC15_/_OSC32_OUT_3") (pintype "bidirectional"))
      (node (ref "Y1") (pin "2") (pinfunction "2_2") (pintype "passive"))
    )
    (net (code "50") (name "Net-(U4-SW-Pad5)") (class "Default")
      (node (ref "U4") (pin "5") (pinfunction "SW_5") (pintype "power_in"))
      (node (ref "U4") (pin "6") (pinfunction "SW_6") (pintype "power_in"))
    )
    (net (code "51") (name "Net-(U4-VCC)") (class "Default")
      (node (ref "C16") (pin "2") (pinfunction "2_2") (pintype "passive"))
      (node (ref "U4") (pin "8") (pinfunction "VCC_8") (pintype "power_in"))
    )
    (net (code "52") (name "VBAT") (class "Default")
      (node (ref "C14") (pin "+") (pinfunction "+_+") (pintype "passive"))
      (node (ref "J2") (pin "1") (pinfunction "1_1") (pintype "passive"))
      (node (ref "Q1") (pin "D") (pinfunction "D_D") (pintype "passive"))
      (node (ref "R17") (pin "2") (pinfunction "2_2") (pintype "passive"))
    )
    (net (code "53") (name "VBAT_MID") (class "Default")
      (node (ref "C2") (pin "2") (pinfunction "2_2") (pintype "passive"))
      (node (ref "C3") (pin "2") (pinfunction "2_2") (pintype "passive"))
      (node (ref "D1") (pin "C") (pinfunction "C_C") (pintype "passive"))
      (node (ref "D3") (pin "C") (pinfunction "C_C") (pintype "passive"))
      (node (ref "Q1") (pin "S") (pinfunction "S_S") (pintype "passive"))
      (node (ref "Q2") (pin "S") (pinfunction "S_S") (pintype "passive"))
      (node (ref "R2") (pin "1") (pinfunction "1_1") (pintype "passive"))
      (node (ref "R5") (pin "1") (pinfunction "1_1") (pintype "passive"))
      (node (ref "U4") (pin "2") (pinfunction "EN_2") (pintype "input"))
      (node (ref "U4") (pin "3") (pinfunction "VIN_3") (pintype "power_in"))
    )
    (net (code "54") (name "VEXT") (class "Default")
      (node (ref "H3") (pin "HOLE") (pinfunction "HOLE_HOLE") (pintype "passive"))
      (node (ref "H6") (pin "HOLE") (pinfunction "HOLE_HOLE") (pintype "passive"))
      (node (ref "Q2") (pin "D") (pinfunction "D_D") (pintype "passive"))
      (node (ref "R14") (pin "2") (pinfunction "2_2") (pintype "passive"))
      (node (ref "R16") (pin "1") (pinfunction "1_1") (pintype "passive"))
      (node (ref "TVS1") (pin "A") (pinfunction "A_A") (pintype "passive"))
    )
    (net (code "55") (name "unconnected-(U1-PA3-Pad9)") (class "Default")
      (node (ref "U1") (pin "9") (pinfunction "PA3_9") (pintype "bidirectional+no_connect"))
    )
    (net (code "56") (name "unconnected-(U1-PA4-Pad10)") (class "Default")
      (node (ref "U1") (pin "10") (pinfunction "PA4_10") (pintype "bidirectional"))
    )
    (net (code "57") (name "unconnected-(U1-PA5-Pad11)") (class "Default")
      (node (ref "U1") (pin "11") (pinfunction "PA5_11") (pintype "bidirectional"))
    )
    (net (code "58") (name "unconnected-(U4-BOOT-Pad7)") (class "Default")
      (node (ref "U4") (pin "7") (pinfunction "BOOT_7") (pintype "power_in+no_connect"))
    )
    (net (code "59") (name "unconnected-(U4-PGOOD-Pad1)") (class "Default")
      (node (ref "U4") (pin "1") (pinfunction "PGOOD_1") (pintype "open_collector+no_connect"))
    )
  )
)
